# valhalla_v0_1.net
KiCad netlist of a schematic drawn in EAGLE
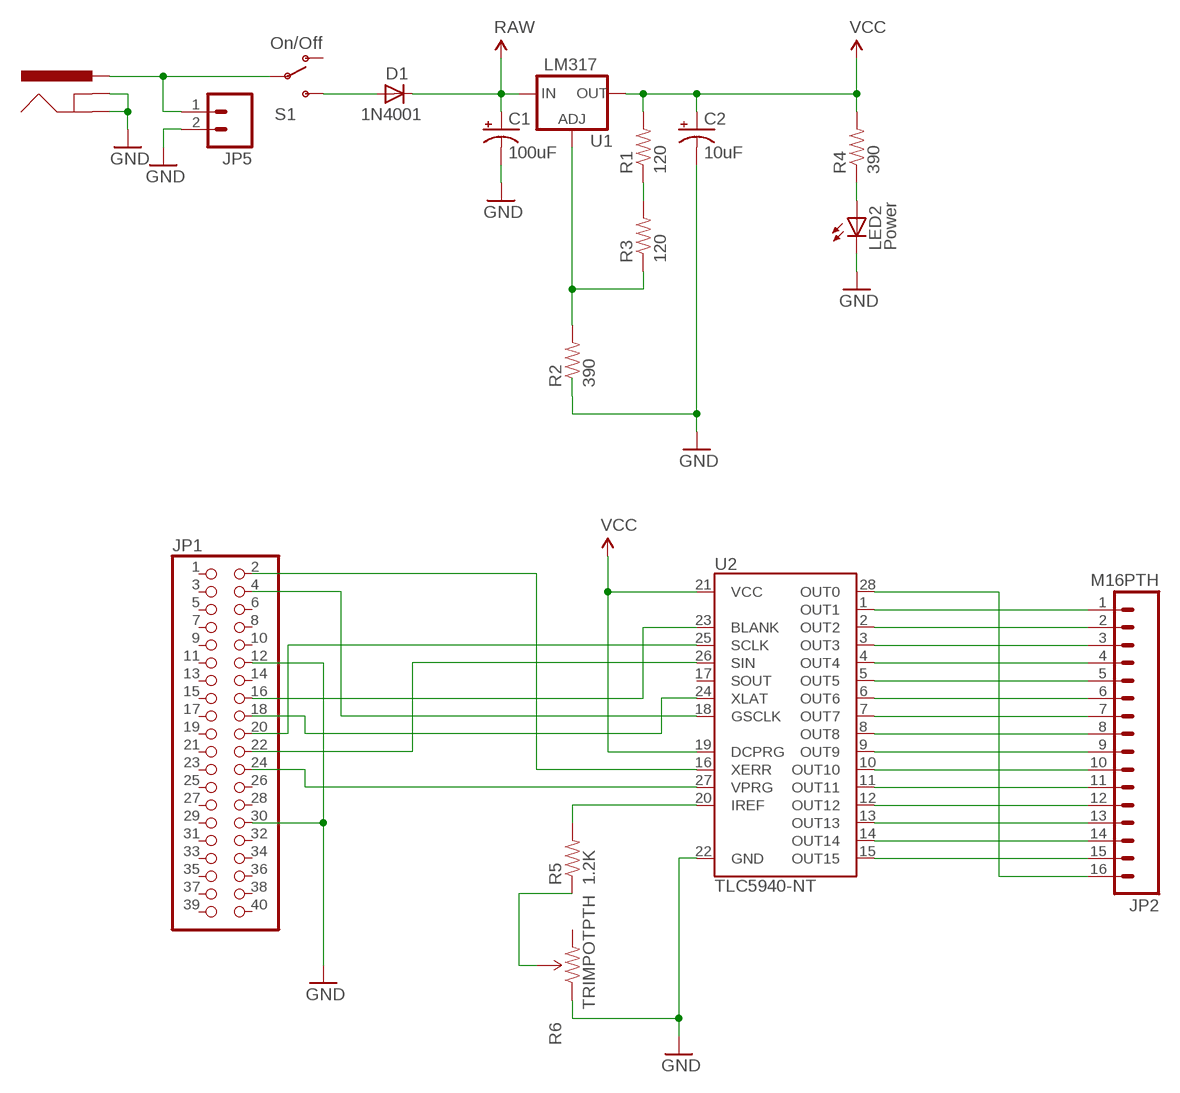
[diagram p0: schematic, sheet 1]

(export (version "E")
  (design (tool "Eeschema 10.0.6"))
  (components
    (comp (ref "C1")
      (value "100uF")
      (footprint "eagle-import:CPOL-RADIAL-100UF-25V")
      (libsource (lib "eagle-import") (part "CAP_POLPTH1"))
    )
    (comp (ref "C2")
      (value "10uF")
      (footprint "eagle-import:CPOL-RADIAL-10UF-25V")
      (libsource (lib "eagle-import") (part "CAP_POLPTH2"))
    )
    (comp (ref "D1")
      (value "1N4001")
      (footprint "eagle-import:DIODE-0.4")
      (libsource (lib "eagle-import") (part "DIODEPTH"))
    )
    (comp (ref "J1")
      (value "POWER_JACKPTH")
      (footprint "eagle-import:POWER_JACK_PTH")
      (libsource (lib "eagle-import") (part "POWER_JACKPTH"))
    )
    (comp (ref "JP1")
      (value "PINHD-2X20")
      (footprint "eagle-import:2X20")
      (libsource (lib "eagle-import") (part "PINHD-2X20"))
    )
    (comp (ref "JP2")
      (value "M16PTH")
      (footprint "eagle-import:1X16")
      (libsource (lib "eagle-import") (part "M16PTH"))
    )
    (comp (ref "JP5")
      (value "M02PTH")
      (footprint "eagle-import:1X02")
      (libsource (lib "eagle-import") (part "M02PTH"))
    )
    (comp (ref "LED2")
      (value "Power")
      (footprint "eagle-import:LED5MM")
      (libsource (lib "eagle-import") (part "LED5MM"))
    )
    (comp (ref "R1")
      (value "120")
      (footprint "eagle-import:AXIAL-0.3")
      (libsource (lib "eagle-import") (part "RESISTORPTH1"))
    )
    (comp (ref "R2")
      (value "390")
      (footprint "eagle-import:AXIAL-0.3")
      (libsource (lib "eagle-import") (part "RESISTORPTH1"))
    )
    (comp (ref "R3")
      (value "120")
      (footprint "eagle-import:AXIAL-0.3")
      (libsource (lib "eagle-import") (part "RESISTORPTH1"))
    )
    (comp (ref "R4")
      (value "390")
      (footprint "eagle-import:AXIAL-0.3")
      (libsource (lib "eagle-import") (part "RESISTORPTH1"))
    )
    (comp (ref "R5")
      (value "1.2K")
      (footprint "eagle-import:AXIAL-0.5")
      (libsource (lib "eagle-import") (part "RESISTORPTH-1/2W"))
    )
    (comp (ref "R6")
      (value "TRIMPOTPTH")
      (footprint "eagle-import:TRIM_POT_PTH")
      (libsource (lib "eagle-import") (part "TRIMPOTPTH"))
    )
    (comp (ref "S1")
      (value "On/Off")
      (footprint "eagle-import:SWITCH-SPST")
      (libsource (lib "eagle-import") (part "SWITCH-SPSTPTH"))
    )
    (comp (ref "U1")
      (value "LM317")
      (footprint "eagle-import:TO220-ADJ")
      (libsource (lib "eagle-import") (part "V_REG_317SINK"))
    )
    (comp (ref "U2")
      (value "TLC5940-NT")
      (footprint "eagle-import:DIL28-3")
      (libsource (lib "eagle-import") (part "TLC5940-NT"))
    )
  )
  (nets
    (net (code "1") (name "GND") (class "Default")
      (node (ref "C1") (pin "2") (pinfunction "-_2") (pintype "passive"))
      (node (ref "C2") (pin "2") (pinfunction "-_2") (pintype "passive"))
      (node (ref "J1") (pin "GND") (pinfunction "GND_GND") (pintype "bidirectional"))
      (node (ref "J1") (pin "GNDBREAK") (pinfunction "GNDBREAK_GNDBREAK") (pintype "bidirectional"))
      (node (ref "JP1") (pin "12") (pinfunction "12_12") (pintype "passive"))
      (node (ref "JP1") (pin "30") (pinfunction "30_30") (pintype "passive"))
      (node (ref "JP5") (pin "2") (pinfunction "2_2") (pintype "passive"))
      (node (ref "LED2") (pin "K") (pinfunction "C_K") (pintype "passive"))
      (node (ref "R2") (pin "P$1") (pinfunction "1_P$1") (pintype "passive"))
      (node (ref "R6") (pin "1") (pinfunction "CCW_1") (pintype "passive"))
      (node (ref "U2") (pin "22") (pinfunction "GND_22") (pintype "bidirectional"))
    )
    (net (code "2") (name "Net-(R1-1)") (class "Default")
      (node (ref "R1") (pin "P$1") (pinfunction "1_P$1") (pintype "passive"))
      (node (ref "R3") (pin "P$2") (pinfunction "2_P$2") (pintype "passive"))
    )
    (net (code "3") (name "Net-(R2-2)") (class "Default")
      (node (ref "R2") (pin "P$2") (pinfunction "2_P$2") (pintype "passive"))
      (node (ref "R3") (pin "P$1") (pinfunction "1_P$1") (pintype "passive"))
      (node (ref "U1") (pin "ADJ") (pinfunction "ADJ_ADJ") (pintype "input"))
    )
    (net (code "4") (name "Net-(R4-1)") (class "Default")
      (node (ref "LED2") (pin "A") (pinfunction "A_A") (pintype "passive"))
      (node (ref "R4") (pin "P$1") (pinfunction "1_P$1") (pintype "passive"))
    )
    (net (code "5") (name "Net-(R5-1)") (class "Default")
      (node (ref "R5") (pin "P$1") (pinfunction "1_P$1") (pintype "passive"))
      (node (ref "R6") (pin "2") (pinfunction "WIPER_2") (pintype "passive"))
    )
    (net (code "6") (name "Net-(R5-2)") (class "Default")
      (node (ref "R5") (pin "P$2") (pinfunction "2_P$2") (pintype "passive"))
      (node (ref "U2") (pin "20") (pinfunction "IREF_20") (pintype "bidirectional"))
    )
    (net (code "7") (name "Net-(S1-P)") (class "Default")
      (node (ref "J1") (pin "PWR") (pinfunction "PWR_PWR") (pintype "bidirectional"))
      (node (ref "JP5") (pin "1") (pinfunction "1_1") (pintype "passive"))
      (node (ref "S1") (pin "2") (pinfunction "P_2") (pintype "passive"))
    )
    (net (code "8") (name "Net-(S1-S)") (class "Default")
      (node (ref "D1") (pin "A") (pinfunction "A_A") (pintype "passive"))
      (node (ref "S1") (pin "3") (pinfunction "S_3") (pintype "passive"))
    )
    (net (code "9") (name "Net-(U2-BLANK)") (class "Default")
      (node (ref "JP1") (pin "16") (pinfunction "16_16") (pintype "passive"))
      (node (ref "U2") (pin "23") (pinfunction "BLANK_23") (pintype "bidirectional"))
    )
    (net (code "10") (name "Net-(U2-GSCLK)") (class "Default")
      (node (ref "JP1") (pin "4") (pinfunction "4_4") (pintype "passive"))
      (node (ref "U2") (pin "18") (pinfunction "GSCLK_18") (pintype "bidirectional"))
    )
    (net (code "11") (name "Net-(U2-OUT0)") (class "Default")
      (node (ref "JP2") (pin "16") (pinfunction "16_16") (pintype "passive"))
      (node (ref "U2") (pin "28") (pinfunction "OUT0_28") (pintype "bidirectional"))
    )
    (net (code "12") (name "Net-(U2-OUT1)") (class "Default")
      (node (ref "JP2") (pin "1") (pinfunction "1_1") (pintype "passive"))
      (node (ref "U2") (pin "1") (pinfunction "OUT1_1") (pintype "bidirectional"))
    )
    (net (code "13") (name "Net-(U2-OUT2)") (class "Default")
      (node (ref "JP2") (pin "2") (pinfunction "2_2") (pintype "passive"))
      (node (ref "U2") (pin "2") (pinfunction "OUT2_2") (pintype "bidirectional"))
    )
    (net (code "14") (name "Net-(U2-OUT3)") (class "Default")
      (node (ref "JP2") (pin "3") (pinfunction "3_3") (pintype "passive"))
      (node (ref "U2") (pin "3") (pinfunction "OUT3_3") (pintype "bidirectional"))
    )
    (net (code "15") (name "Net-(U2-OUT4)") (class "Default")
      (node (ref "JP2") (pin "4") (pinfunction "4_4") (pintype "passive"))
      (node (ref "U2") (pin "4") (pinfunction "OUT4_4") (pintype "bidirectional"))
    )
    (net (code "16") (name "Net-(U2-OUT5)") (class "Default")
      (node (ref "JP2") (pin "5") (pinfunction "5_5") (pintype "passive"))
      (node (ref "U2") (pin "5") (pinfunction "OUT5_5") (pintype "bidirectional"))
    )
    (net (code "17") (name "Net-(U2-OUT6)") (class "Default")
      (node (ref "JP2") (pin "6") (pinfunction "6_6") (pintype "passive"))
      (node (ref "U2") (pin "6") (pinfunction "OUT6_6") (pintype "bidirectional"))
    )
    (net (code "18") (name "Net-(U2-OUT7)") (class "Default")
      (node (ref "JP2") (pin "7") (pinfunction "7_7") (pintype "passive"))
      (node (ref "U2") (pin "7") (pinfunction "OUT7_7") (pintype "bidirectional"))
    )
    (net (code "19") (name "Net-(U2-OUT8)") (class "Default")
      (node (ref "JP2") (pin "8") (pinfunction "8_8") (pintype "passive"))
      (node (ref "U2") (pin "8") (pinfunction "OUT8_8") (pintype "bidirectional"))
    )
    (net (code "20") (name "Net-(U2-OUT9)") (class "Default")
      (node (ref "JP2") (pin "9") (pinfunction "9_9") (pintype "passive"))
      (node (ref "U2") (pin "9") (pinfunction "OUT9_9") (pintype "bidirectional"))
    )
    (net (code "21") (name "Net-(U2-OUT10)") (class "Default")
      (node (ref "JP2") (pin "10") (pinfunction "10_10") (pintype "passive"))
      (node (ref "U2") (pin "10") (pinfunction "OUT10_10") (pintype "bidirectional"))
    )
    (net (code "22") (name "Net-(U2-OUT11)") (class "Default")
      (node (ref "JP2") (pin "11") (pinfunction "11_11") (pintype "passive"))
      (node (ref "U2") (pin "11") (pinfunction "OUT11_11") (pintype "bidirectional"))
    )
    (net (code "23") (name "Net-(U2-OUT12)") (class "Default")
      (node (ref "JP2") (pin "12") (pinfunction "12_12") (pintype "passive"))
      (node (ref "U2") (pin "12") (pinfunction "OUT12_12") (pintype "bidirectional"))
    )
    (net (code "24") (name "Net-(U2-OUT13)") (class "Default")
      (node (ref "JP2") (pin "13") (pinfunction "13_13") (pintype "passive"))
      (node (ref "U2") (pin "13") (pinfunction "OUT13_13") (pintype "bidirectional"))
    )
    (net (code "25") (name "Net-(U2-OUT14)") (class "Default")
      (node (ref "JP2") (pin "14") (pinfunction "14_14") (pintype "passive"))
      (node (ref "U2") (pin "14") (pinfunction "OUT14_14") (pintype "bidirectional"))
    )
    (net (code "26") (name "Net-(U2-OUT15)") (class "Default")
      (node (ref "JP2") (pin "15") (pinfunction "15_15") (pintype "passive"))
      (node (ref "U2") (pin "15") (pinfunction "OUT15_15") (pintype "bidirectional"))
    )
    (net (code "27") (name "Net-(U2-SCLK)") (class "Default")
      (node (ref "JP1") (pin "20") (pinfunction "20_20") (pintype "passive"))
      (node (ref "U2") (pin "25") (pinfunction "SCLK_25") (pintype "bidirectional"))
    )
    (net (code "28") (name "Net-(U2-SIN)") (class "Default")
      (node (ref "JP1") (pin "22") (pinfunction "22_22") (pintype "passive"))
      (node (ref "U2") (pin "26") (pinfunction "SIN_26") (pintype "bidirectional"))
    )
    (net (code "29") (name "Net-(U2-VPRG)") (class "Default")
      (node (ref "JP1") (pin "24") (pinfunction "24_24") (pintype "passive"))
      (node (ref "U2") (pin "27") (pinfunction "VPRG_27") (pintype "bidirectional"))
    )
    (net (code "30") (name "Net-(U2-XERR)") (class "Default")
      (node (ref "JP1") (pin "2") (pinfunction "2_2") (pintype "passive"))
      (node (ref "U2") (pin "16") (pinfunction "XERR_16") (pintype "bidirectional"))
    )
    (net (code "31") (name "Net-(U2-XLAT)") (class "Default")
      (node (ref "JP1") (pin "18") (pinfunction "18_18") (pintype "passive"))
      (node (ref "U2") (pin "24") (pinfunction "XLAT_24") (pintype "bidirectional"))
    )
    (net (code "32") (name "RAW") (class "Default")
      (node (ref "C1") (pin "1") (pinfunction "+_1") (pintype "passive"))
      (node (ref "D1") (pin "C") (pinfunction "C_C") (pintype "passive"))
      (node (ref "U1") (pin "IN") (pinfunction "IN_IN") (pintype "input"))
    )
    (net (code "33") (name "VCC") (class "Default")
      (node (ref "C2") (pin "1") (pinfunction "+_1") (pintype "passive"))
      (node (ref "R1") (pin "P$2") (pinfunction "2_P$2") (pintype "passive"))
      (node (ref "R4") (pin "P$2") (pinfunction "2_P$2") (pintype "passive"))
      (node (ref "U1") (pin "OUT") (pinfunction "OUT_OUT") (pintype "output"))
      (node (ref "U2") (pin "19") (pinfunction "DCPRG_19") (pintype "bidirectional"))
      (node (ref "U2") (pin "21") (pinfunction "VCC_21") (pintype "bidirectional"))
    )
    (net (code "34") (name "unconnected-(JP1-Pad1)") (class "Default")
      (node (ref "JP1") (pin "1") (pinfunction "1_1") (pintype "passive"))
    )
    (net (code "35") (name "unconnected-(JP1-Pad3)") (class "Default")
      (node (ref "JP1") (pin "3") (pinfunction "3_3") (pintype "passive"))
    )
    (net (code "36") (name "unconnected-(JP1-Pad5)") (class "Default")
      (node (ref "JP1") (pin "5") (pinfunction "5_5") (pintype "passive"))
    )
    (net (code "37") (name "unconnected-(JP1-Pad6)") (class "Default")
      (node (ref "JP1") (pin "6") (pinfunction "6_6") (pintype "passive"))
    )
    (net (code "38") (name "unconnected-(JP1-Pad7)") (class "Default")
      (node (ref "JP1") (pin "7") (pinfunction "7_7") (pintype "passive"))
    )
    (net (code "39") (name "unconnected-(JP1-Pad8)") (class "Default")
      (node (ref "JP1") (pin "8") (pinfunction "8_8") (pintype "passive"))
    )
    (net (code "40") (name "unconnected-(JP1-Pad9)") (class "Default")
      (node (ref "JP1") (pin "9") (pinfunction "9_9") (pintype "passive"))
    )
    (net (code "41") (name "unconnected-(JP1-Pad10)") (class "Default")
      (node (ref "JP1") (pin "10") (pinfunction "10_10") (pintype "passive"))
    )
    (net (code "42") (name "unconnected-(JP1-Pad11)") (class "Default")
      (node (ref "JP1") (pin "11") (pinfunction "11_11") (pintype "passive"))
    )
    (net (code "43") (name "unconnected-(JP1-Pad13)") (class "Default")
      (node (ref "JP1") (pin "13") (pinfunction "13_13") (pintype "passive"))
    )
    (net (code "44") (name "unconnected-(JP1-Pad14)") (class "Default")
      (node (ref "JP1") (pin "14") (pinfunction "14_14") (pintype "passive"))
    )
    (net (code "45") (name "unconnected-(JP1-Pad15)") (class "Default")
      (node (ref "JP1") (pin "15") (pinfunction "15_15") (pintype "passive"))
    )
    (net (code "46") (name "unconnected-(JP1-Pad17)") (class "Default")
      (node (ref "JP1") (pin "17") (pinfunction "17_17") (pintype "passive"))
    )
    (net (code "47") (name "unconnected-(JP1-Pad19)") (class "Default")
      (node (ref "JP1") (pin "19") (pinfunction "19_19") (pintype "passive"))
    )
    (net (code "48") (name "unconnected-(JP1-Pad21)") (class "Default")
      (node (ref "JP1") (pin "21") (pinfunction "21_21") (pintype "passive"))
    )
    (net (code "49") (name "unconnected-(JP1-Pad23)") (class "Default")
      (node (ref "JP1") (pin "23") (pinfunction "23_23") (pintype "passive"))
    )
    (net (code "50") (name "unconnected-(JP1-Pad25)") (class "Default")
      (node (ref "JP1") (pin "25") (pinfunction "25_25") (pintype "passive"))
    )
    (net (code "51") (name "unconnected-(JP1-Pad26)") (class "Default")
      (node (ref "JP1") (pin "26") (pinfunction "26_26") (pintype "passive"))
    )
    (net (code "52") (name "unconnected-(JP1-Pad27)") (class "Default")
      (node (ref "JP1") (pin "27") (pinfunction "27_27") (pintype "passive"))
    )
    (net (code "53") (name "unconnected-(JP1-Pad28)") (class "Default")
      (node (ref "JP1") (pin "28") (pinfunction "28_28") (pintype "passive"))
    )
    (net (code "54") (name "unconnected-(JP1-Pad29)") (class "Default")
      (node (ref "JP1") (pin "29") (pinfunction "29_29") (pintype "passive"))
    )
    (net (code "55") (name "unconnected-(JP1-Pad31)") (class "Default")
      (node (ref "JP1") (pin "31") (pinfunction "31_31") (pintype "passive"))
    )
    (net (code "56") (name "unconnected-(JP1-Pad32)") (class "Default")
      (node (ref "JP1") (pin "32") (pinfunction "32_32") (pintype "passive"))
    )
    (net (code "57") (name "unconnected-(JP1-Pad33)") (class "Default")
      (node (ref "JP1") (pin "33") (pinfunction "33_33") (pintype "passive"))
    )
    (net (code "58") (name "unconnected-(JP1-Pad34)") (class "Default")
      (node (ref "JP1") (pin "34") (pinfunction "34_34") (pintype "passive"))
    )
    (net (code "59") (name "unconnected-(JP1-Pad35)") (class "Default")
      (node (ref "JP1") (pin "35") (pinfunction "35_35") (pintype "passive"))
    )
    (net (code "60") (name "unconnected-(JP1-Pad36)") (class "Default")
      (node (ref "JP1") (pin "36") (pinfunction "36_36") (pintype "passive"))
    )
    (net (code "61") (name "unconnected-(JP1-Pad37)") (class "Default")
      (node (ref "JP1") (pin "37") (pinfunction "37_37") (pintype "passive"))
    )
    (net (code "62") (name "unconnected-(JP1-Pad38)") (class "Default")
      (node (ref "JP1") (pin "38") (pinfunction "38_38") (pintype "passive"))
    )
    (net (code "63") (name "unconnected-(JP1-Pad39)") (class "Default")
      (node (ref "JP1") (pin "39") (pinfunction "39_39") (pintype "passive"))
    )
    (net (code "64") (name "unconnected-(JP1-Pad40)") (class "Default")
      (node (ref "JP1") (pin "40") (pinfunction "40_40") (pintype "passive"))
    )
    (net (code "65") (name "unconnected-(R6-CW-Pad3)") (class "Default")
      (node (ref "R6") (pin "3") (pinfunction "CW_3") (pintype "passive"))
    )
    (net (code "66") (name "unconnected-(S1-O-Pad1)") (class "Default")
      (node (ref "S1") (pin "1") (pinfunction "O_1") (pintype "passive"))
    )
    (net (code "67") (name "unconnected-(U2-SOUT-Pad17)") (class "Default")
      (node (ref "U2") (pin "17") (pinfunction "SOUT_17") (pintype "bidirectional"))
    )
  )
)
